# Power_Board.net
KiCad netlist of a schematic drawn in Altium Designer
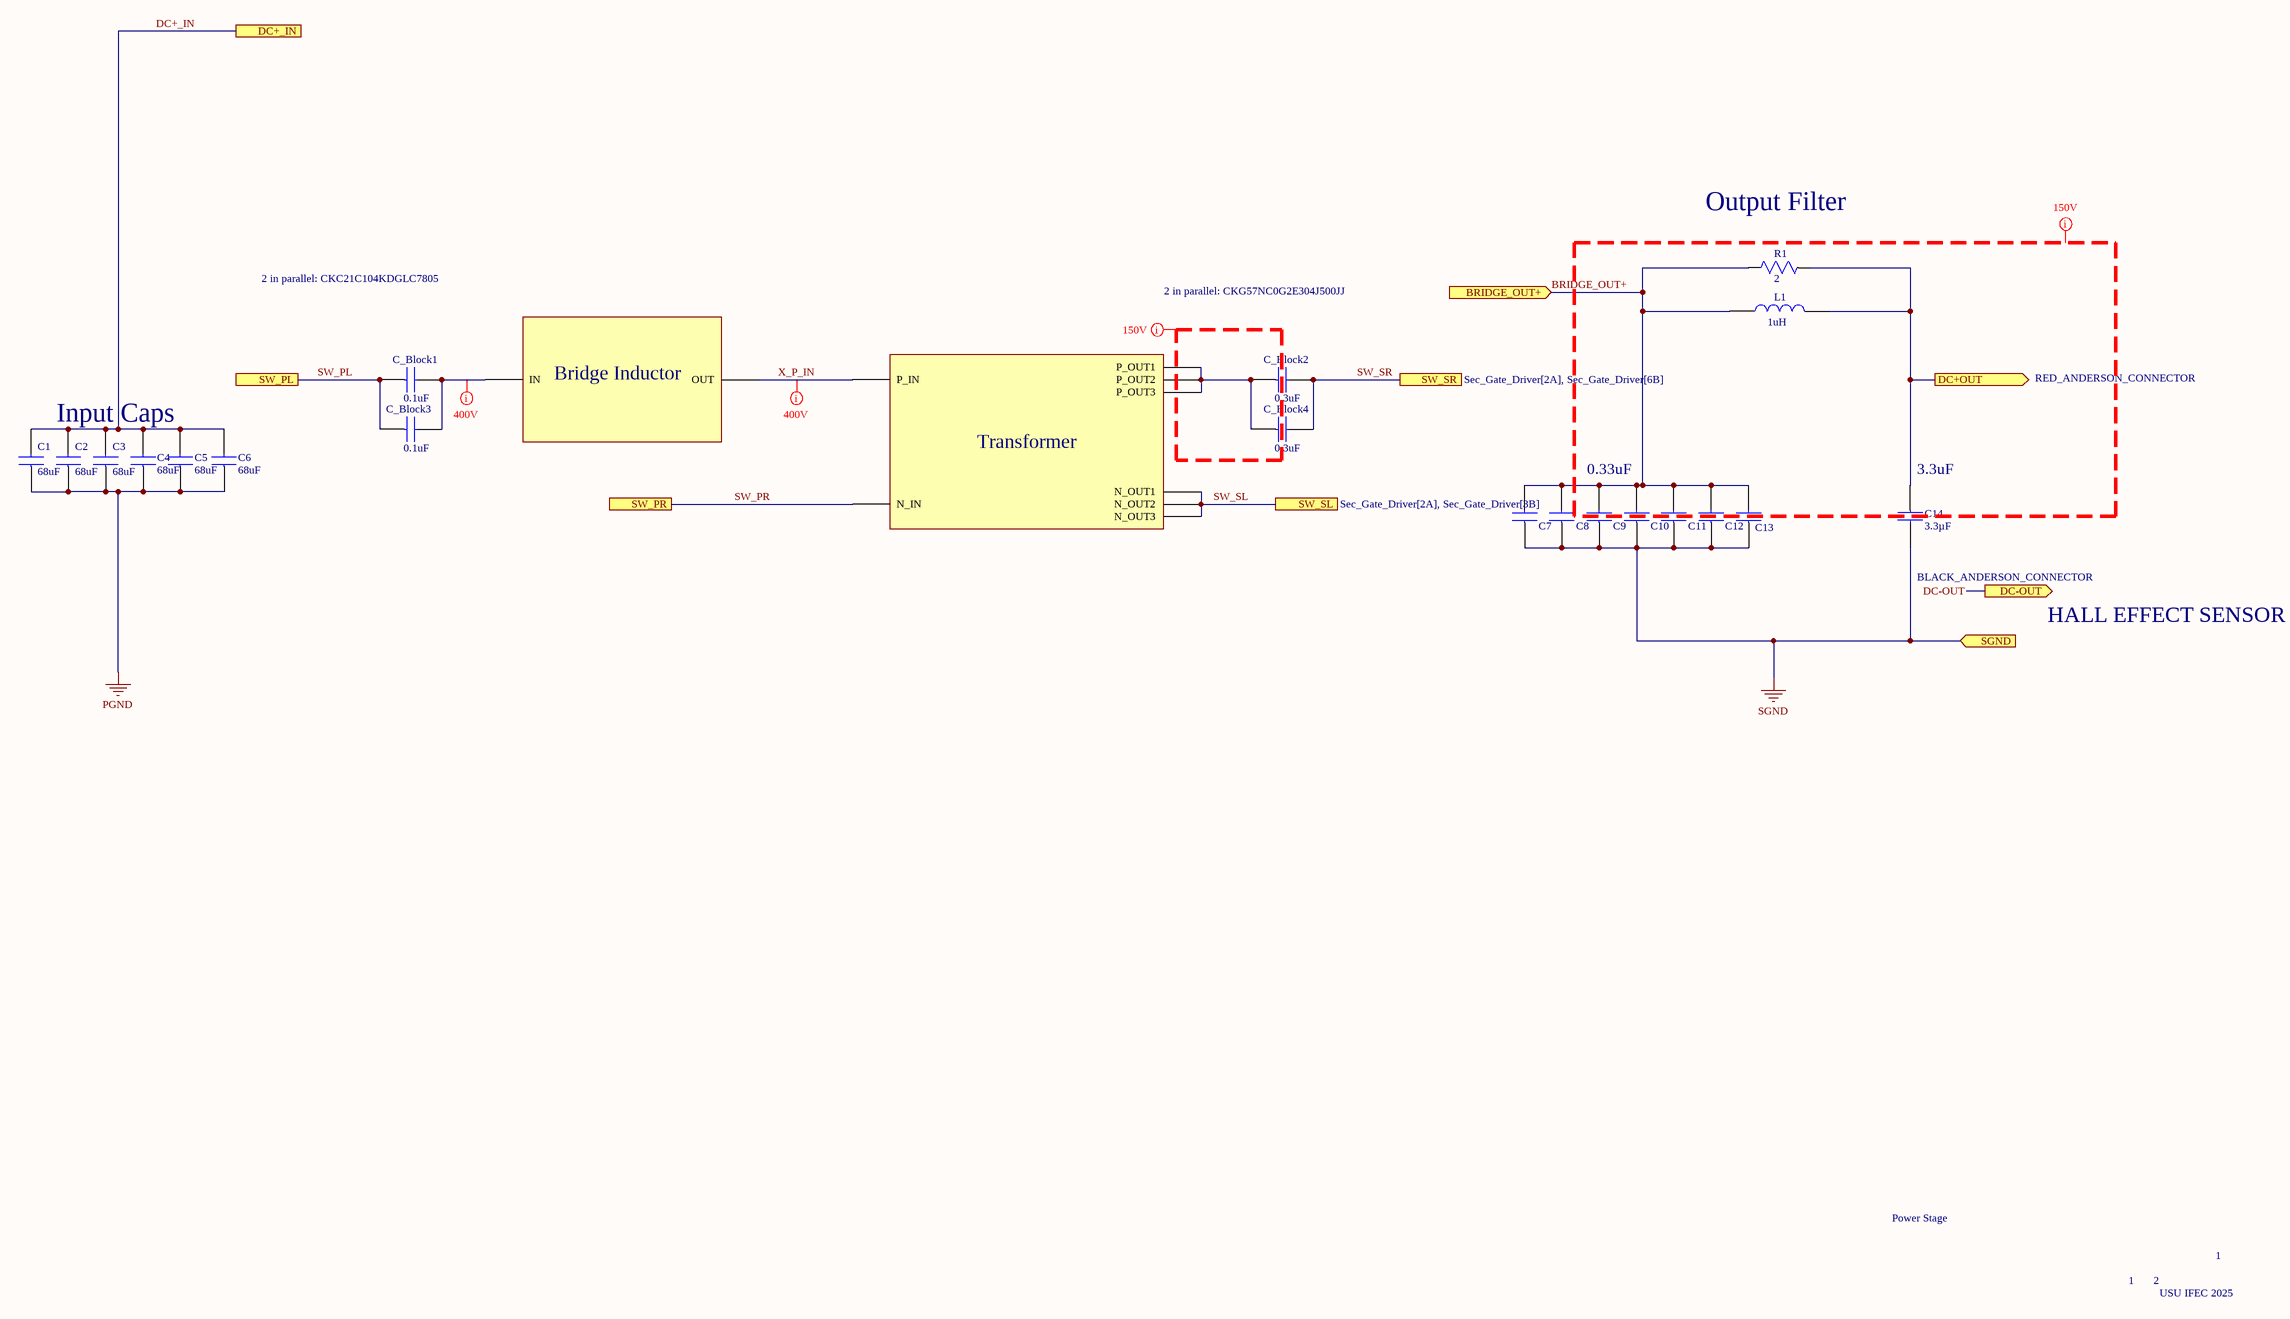
[diagram p0: Power_Board.SchDoc]

(export (version "E")
  (design (tool "Eeschema 10.0.6"))
  (components
    (comp (ref "C1")
      (value "68uF")
      (footprint "CAP_L_18X20_RUB")
      (description "CAP ALUM 68UF 20% 450V RADIAL TH")
      (libsource (lib "DAB") (part "450LXW68MEFR18X20"))
    )
    (comp (ref "C2")
      (value "68uF")
      (footprint "CAP_L_18X20_RUB")
      (description "CAP ALUM 68UF 20% 450V RADIAL TH")
      (libsource (lib "DAB") (part "450LXW68MEFR18X20"))
    )
    (comp (ref "C3")
      (value "68uF")
      (footprint "CAP_L_18X20_RUB")
      (description "CAP ALUM 68UF 20% 450V RADIAL TH")
      (libsource (lib "DAB") (part "450LXW68MEFR18X20"))
    )
    (comp (ref "C4")
      (value "68uF")
      (footprint "CAP_L_18X20_RUB")
      (description "CAP ALUM 68UF 20% 450V RADIAL TH")
      (libsource (lib "DAB") (part "450LXW68MEFR18X20"))
    )
    (comp (ref "C5")
      (value "68uF")
      (footprint "CAP_L_18X20_RUB")
      (description "CAP ALUM 68UF 20% 450V RADIAL TH")
      (libsource (lib "DAB") (part "450LXW68MEFR18X20"))
    )
    (comp (ref "C6")
      (value "68uF")
      (footprint "CAP_L_18X20_RUB")
      (description "CAP ALUM 68UF 20% 450V RADIAL TH")
      (libsource (lib "DAB") (part "450LXW68MEFR18X20"))
    )
    (comp (ref "C7")
      (value "0.047uF")
      (footprint "C1206")
      (description "CAP CER 0.047UF 500V X7R 1206")
      (fields
        (field (name "MANUFACTURER_PART_NUMBER") "C1206C473KCRACTU")
        (field (name "MOUSER PART NUMBER") "80-C1206C473KCRACTU")
      )
      (libsource (lib "DAB") (part "C1206C473KCRACTU"))
    )
    (comp (ref "C8")
      (value "0.047uF")
      (footprint "C1206")
      (description "CAP CER 0.047UF 500V X7R 1206")
      (fields
        (field (name "MANUFACTURER_PART_NUMBER") "C1206C473KCRACTU")
        (field (name "MOUSER PART NUMBER") "80-C1206C473KCRACTU")
      )
      (libsource (lib "DAB") (part "C1206C473KCRACTU"))
    )
    (comp (ref "C9")
      (value "0.047uF")
      (footprint "C1206")
      (description "CAP CER 0.047UF 500V X7R 1206")
      (fields
        (field (name "MANUFACTURER_PART_NUMBER") "C1206C473KCRACTU")
        (field (name "MOUSER PART NUMBER") "80-C1206C473KCRACTU")
      )
      (libsource (lib "DAB") (part "C1206C473KCRACTU"))
    )
    (comp (ref "C10")
      (value "0.047uF")
      (footprint "C1206")
      (description "CAP CER 0.047UF 500V X7R 1206")
      (fields
        (field (name "MANUFACTURER_PART_NUMBER") "C1206C473KCRACTU")
        (field (name "MOUSER PART NUMBER") "80-C1206C473KCRACTU")
      )
      (libsource (lib "DAB") (part "C1206C473KCRACTU"))
    )
    (comp (ref "C11")
      (value "0.047uF")
      (footprint "C1206")
      (description "CAP CER 0.047UF 500V X7R 1206")
      (fields
        (field (name "MANUFACTURER_PART_NUMBER") "C1206C473KCRACTU")
        (field (name "MOUSER PART NUMBER") "80-C1206C473KCRACTU")
      )
      (libsource (lib "DAB") (part "C1206C473KCRACTU"))
    )
    (comp (ref "C12")
      (value "0.047uF")
      (footprint "C1206")
      (description "CAP CER 0.047UF 500V X7R 1206")
      (fields
        (field (name "MANUFACTURER_PART_NUMBER") "C1206C473KCRACTU")
        (field (name "MOUSER PART NUMBER") "80-C1206C473KCRACTU")
      )
      (libsource (lib "DAB") (part "C1206C473KCRACTU"))
    )
    (comp (ref "C13")
      (value "0.047uF")
      (footprint "C1206")
      (description "CAP CER 0.047UF 500V X7R 1206")
      (fields
        (field (name "MANUFACTURER_PART_NUMBER") "C1206C473KCRACTU")
        (field (name "MOUSER PART NUMBER") "80-C1206C473KCRACTU")
      )
      (libsource (lib "DAB") (part "C1206C473KCRACTU"))
    )
    (comp (ref "C14")
      (value "3.3µF")
      (footprint "Power_Board:CAPC4632X300N")
      (description "CUSTOM FOOTPRINT")
      (fields
        (field (name "MANUFACTURER_PART_NUMBER") "885382211003")
        (field (name "MOUSER PART NUMBER") "710-885382211003")
      )
      (libsource (lib "Power_Board") (part "885382211003"))
    )
    (comp (ref "C_Block1")
      (value "0.1uF")
      (footprint "CAPC5777X540N")
      (description "CAP CER 0.1UF 1KV C0G/NP0 2220")
      (fields
        (field (name "MANUFACTURER_PART_NUMBER") "C1206C473KCRACTU")
        (field (name "MOUSER PART NUMBER") "80-C1206C473KCRACTU")
      )
      (libsource (lib "Power_Board") (part "CKC21C104KDGLC7805"))
    )
    (comp (ref "C_Block2")
      (value "0.3uF")
      (footprint "CAPC6050X550N")
      (description "CAP CER 0.3UF 250V C0G/NP0 SMD")
      (fields
        (field (name "MANUFACTURER_PART_NUMBER") "C1206C473KCRACTU")
        (field (name "MOUSER PART NUMBER") "80-C1206C473KCRACTU")
      )
      (libsource (lib "Power_Board") (part "CKG57NC0G2E304J500JJ"))
    )
    (comp (ref "C_Block3")
      (value "0.1uF")
      (footprint "CAPC5777X540N")
      (description "CAP CER 0.1UF 1KV C0G/NP0 2220")
      (fields
        (field (name "MANUFACTURER_PART_NUMBER") "C1206C473KCRACTU")
        (field (name "MOUSER PART NUMBER") "80-C1206C473KCRACTU")
      )
      (libsource (lib "Power_Board") (part "CKC21C104KDGLC7805"))
    )
    (comp (ref "C_Block4")
      (value "0.3uF")
      (footprint "CAPC6050X550N")
      (description "CAP CER 0.3UF 250V C0G/NP0 SMD")
      (fields
        (field (name "MANUFACTURER_PART_NUMBER") "C1206C473KCRACTU")
        (field (name "MOUSER PART NUMBER") "80-C1206C473KCRACTU")
      )
      (libsource (lib "Power_Board") (part "CKG57NC0G2E304J500JJ"))
    )
    (comp (ref "L1")
      (value "1uH")
      (footprint "INDPM7166X300N")
      (description "FIXED IND 1UH 15A 9.2 MOHM SMD")
      (fields
        (field (name "MANUFACTURER_PART_NUMBER") "ECS-MPIL0630-1R0MC")
        (field (name "MOUSER PART NUMBER") "520-MPIL0630-1R0MC")
      )
      (libsource (lib "DAB") (part "ECS-MPIL0630-1R0MC"))
    )
    (comp (ref "L_Bridge1")
      (value "Bridge Inductor")
      (footprint "Bridge Inductor")
      (libsource (lib "DAB") (part "Bridge Inductor"))
    )
    (comp (ref "R1")
      (value "2")
      (footprint "RESC6331X80N")
      (description "2 Ohms ±1% 2W Chip Resistor 2512 (6432 Metric) Current Sense Thick Film")
      (fields
        (field (name "MANUFACTURER_PART_NUMBER") "CRM2512-FX-2R00ELF")
        (field (name "MOUSER PART NUMBER") "652-CRM2512FX2R00ELF")
      )
      (libsource (lib "DAB") (part "CRM2512-FX-2R00ELF"))
    )
    (comp (ref "XFMR1")
      (value "Transformer")
      (footprint "Transformer")
      (libsource (lib "DAB") (part "Transformer"))
    )
  )
  (nets
    (net (code "1") (name "/BRIDGE_OUT+") (class "Default")
      (node (ref "C10") (pin "2") (pinfunction "2_2") (pintype "passive"))
      (node (ref "C11") (pin "2") (pinfunction "2_2") (pintype "passive"))
      (node (ref "C12") (pin "2") (pinfunction "2_2") (pintype "passive"))
      (node (ref "C13") (pin "2") (pinfunction "2_2") (pintype "passive"))
      (node (ref "C7") (pin "2") (pinfunction "2_2") (pintype "passive"))
      (node (ref "C8") (pin "2") (pinfunction "2_2") (pintype "passive"))
      (node (ref "C9") (pin "2") (pinfunction "2_2") (pintype "passive"))
      (node (ref "L1") (pin "1") (pinfunction "1_1") (pintype "passive"))
      (node (ref "R1") (pin "1") (pinfunction "1_1") (pintype "passive"))
    )
    (net (code "2") (name "/DC+OUT") (class "Default")
      (node (ref "C14") (pin "1") (pinfunction "1_1") (pintype "passive"))
      (node (ref "L1") (pin "2") (pinfunction "2_2") (pintype "passive"))
      (node (ref "R1") (pin "2") (pinfunction "2_2") (pintype "passive"))
    )
    (net (code "3") (name "/DC+_IN") (class "Default")
      (node (ref "C1") (pin "2") (pinfunction "2_2") (pintype "passive"))
      (node (ref "C2") (pin "2") (pinfunction "2_2") (pintype "passive"))
      (node (ref "C3") (pin "2") (pinfunction "2_2") (pintype "passive"))
      (node (ref "C4") (pin "2") (pinfunction "2_2") (pintype "passive"))
      (node (ref "C5") (pin "2") (pinfunction "2_2") (pintype "passive"))
      (node (ref "C6") (pin "2") (pinfunction "2_2") (pintype "passive"))
    )
    (net (code "5") (name "/SW_PL") (class "Default")
      (node (ref "C_Block1") (pin "1") (pinfunction "1_1") (pintype "passive"))
      (node (ref "C_Block3") (pin "1") (pinfunction "1_1") (pintype "passive"))
    )
    (net (code "6") (name "/SW_PR") (class "Default")
      (node (ref "XFMR1") (pin "2") (pinfunction "N_IN_2") (pintype "passive"))
    )
    (net (code "7") (name "/SW_SL") (class "Default")
      (node (ref "XFMR1") (pin "6") (pinfunction "N_OUT1_6") (pintype "passive"))
      (node (ref "XFMR1") (pin "7") (pinfunction "N_OUT2_7") (pintype "passive"))
      (node (ref "XFMR1") (pin "8") (pinfunction "N_OUT3_8") (pintype "passive"))
    )
    (net (code "8") (name "/SW_SR") (class "Default")
      (node (ref "C_Block2") (pin "2") (pinfunction "2_2") (pintype "passive"))
      (node (ref "C_Block4") (pin "2") (pinfunction "2_2") (pintype "passive"))
    )
    (net (code "9") (name "/X_P_IN") (class "Default")
      (node (ref "L_Bridge1") (pin "2") (pinfunction "OUT_2") (pintype "passive"))
      (node (ref "XFMR1") (pin "1") (pinfunction "P_IN_1") (pintype "passive"))
    )
    (net (code "10") (name "Net-(L_Bridge1-IN)") (class "Default")
      (node (ref "C_Block1") (pin "2") (pinfunction "2_2") (pintype "passive"))
      (node (ref "C_Block3") (pin "2") (pinfunction "2_2") (pintype "passive"))
      (node (ref "L_Bridge1") (pin "1") (pinfunction "IN_1") (pintype "passive"))
    )
    (net (code "11") (name "Net-(XFMR1-P_OUT1)") (class "Default")
      (node (ref "C_Block2") (pin "1") (pinfunction "1_1") (pintype "passive"))
      (node (ref "C_Block4") (pin "1") (pinfunction "1_1") (pintype "passive"))
      (node (ref "XFMR1") (pin "3") (pinfunction "P_OUT1_3") (pintype "passive"))
      (node (ref "XFMR1") (pin "4") (pinfunction "P_OUT2_4") (pintype "passive"))
      (node (ref "XFMR1") (pin "5") (pinfunction "P_OUT3_5") (pintype "passive"))
    )
    (net (code "12") (name "PGND") (class "Default")
      (node (ref "C1") (pin "1") (pinfunction "1_1") (pintype "passive"))
      (node (ref "C2") (pin "1") (pinfunction "1_1") (pintype "passive"))
      (node (ref "C3") (pin "1") (pinfunction "1_1") (pintype "passive"))
      (node (ref "C4") (pin "1") (pinfunction "1_1") (pintype "passive"))
      (node (ref "C5") (pin "1") (pinfunction "1_1") (pintype "passive"))
      (node (ref "C6") (pin "1") (pinfunction "1_1") (pintype "passive"))
    )
    (net (code "13") (name "SGND") (class "Default")
      (node (ref "C10") (pin "1") (pinfunction "1_1") (pintype "passive"))
      (node (ref "C11") (pin "1") (pinfunction "1_1") (pintype "passive"))
      (node (ref "C12") (pin "1") (pinfunction "1_1") (pintype "passive"))
      (node (ref "C13") (pin "1") (pinfunction "1_1") (pintype "passive"))
      (node (ref "C14") (pin "2") (pinfunction "2_2") (pintype "passive"))
      (node (ref "C7") (pin "1") (pinfunction "1_1") (pintype "passive"))
      (node (ref "C8") (pin "1") (pinfunction "1_1") (pintype "passive"))
      (node (ref "C9") (pin "1") (pinfunction "1_1") (pintype "passive"))
    )
  )
)
